# USB.net
KiCad netlist of a schematic drawn in Altium Designer
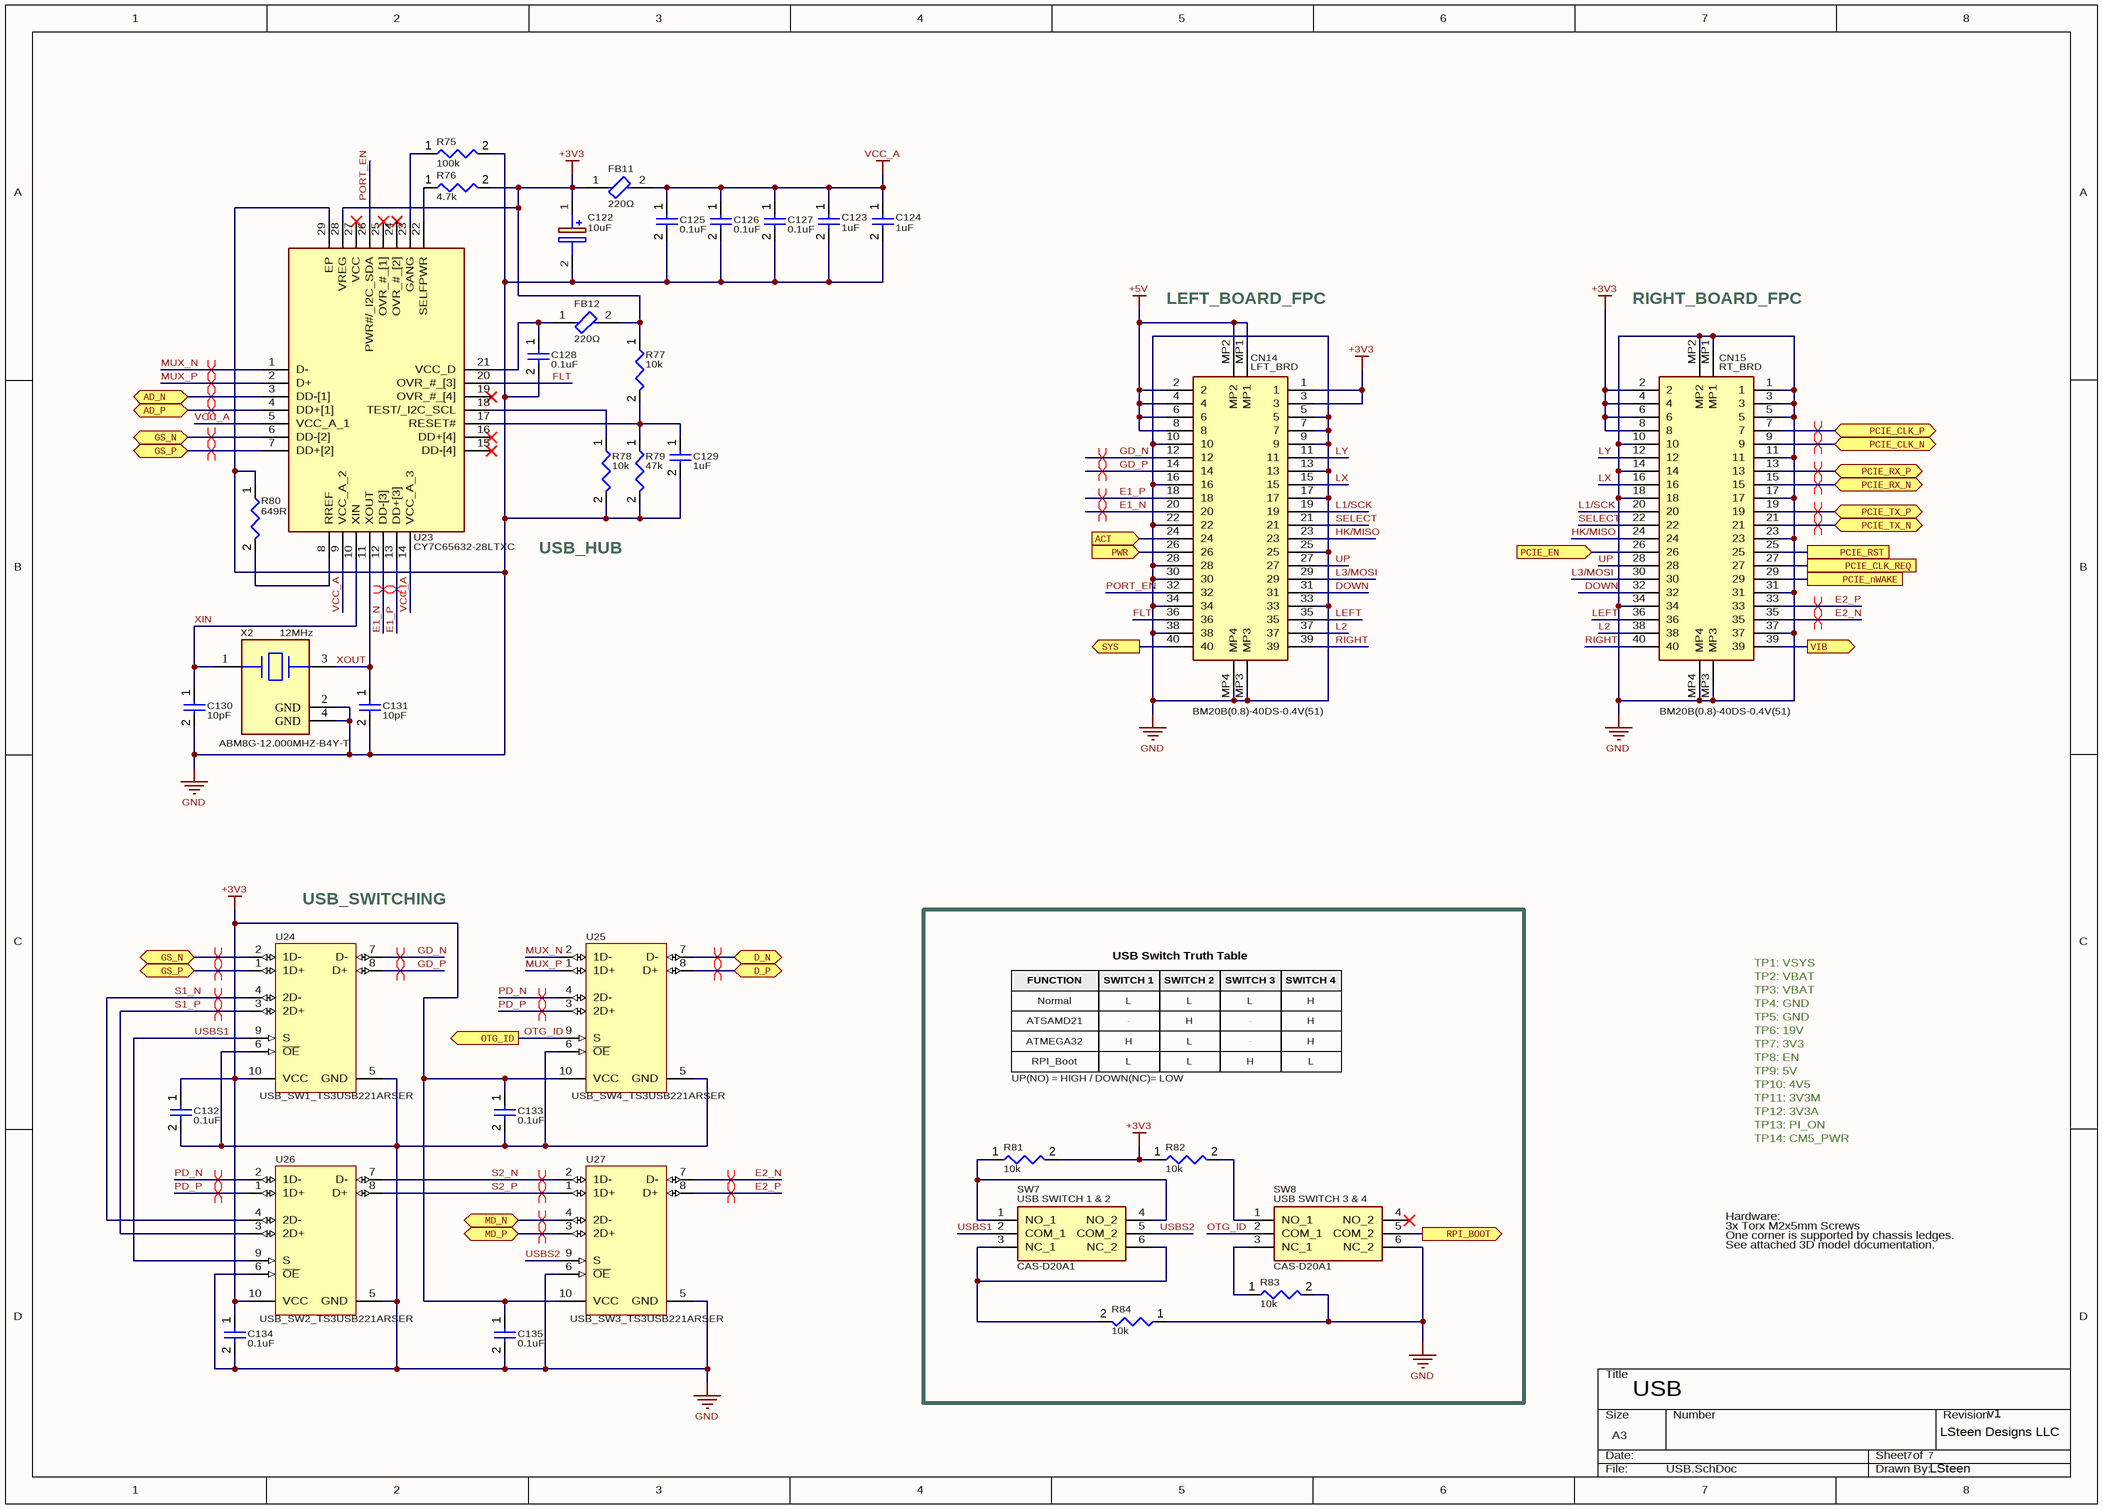
[diagram p0: USB.SchDoc]

(export (version "E")
  (design (tool "Eeschema 10.0.6"))
  (components
    (comp (ref "C122")
      (value "10uF")
      (footprint "SamacSys:CAPAE430X395N")
      (description "Capacitor Polarised")
      (fields
        (field (name "MANUFACTURER_PART_NUMBER") "UZG1C100MCL1GB")
        (field (name "MOUSER PART NUMBER") "647-UZG1C100MCL1GB")
      )
      (libsource (lib "SamacSys") (part "UZG1C100MCL1GB"))
    )
    (comp (ref "C123")
      (value "1uF")
      (footprint "CAPC0603(1608)100_L")
      (description "Chip Capacitor, 1uF +/-20%, 10V, 0603, Thickness 1 mm")
      (fields (field (name "TOLERANCE") "10%"))
      (libsource (lib "Colorado Technical University") (part "CAP-NP-2"))
    )
    (comp (ref "C124")
      (value "1uF")
      (footprint "CAPC0603(1608)100_L")
      (description "Chip Capacitor, 1uF +/-20%, 10V, 0603, Thickness 1 mm")
      (fields (field (name "TOLERANCE") "10%"))
      (libsource (lib "Colorado Technical University") (part "CAP-NP-2"))
    )
    (comp (ref "C125")
      (value "0.1uF")
      (footprint "CAPC1005X56X25LL10T15")
      (description "Chip Capacitor, 0.1 uF, +/- 5%, 16 V, 0402 (1005 Metric)")
      (fields (field (name "TOLERANCE") "5%"))
      (libsource (lib "Colorado Technical University") (part "CAP-NP-2"))
    )
    (comp (ref "C126")
      (value "0.1uF")
      (footprint "CAPC1005X56X25LL10T15")
      (description "Chip Capacitor, 0.1 uF, +/- 5%, 16 V, 0402 (1005 Metric)")
      (fields (field (name "TOLERANCE") "5%"))
      (libsource (lib "Colorado Technical University") (part "CAP-NP-2"))
    )
    (comp (ref "C127")
      (value "0.1uF")
      (footprint "CAPC1005X56X25LL10T15")
      (description "Chip Capacitor, 0.1 uF, +/- 5%, 16 V, 0402 (1005 Metric)")
      (fields (field (name "TOLERANCE") "5%"))
      (libsource (lib "Colorado Technical University") (part "CAP-NP-2"))
    )
    (comp (ref "C128")
      (value "0.1uF")
      (footprint "CAPC1005X56X25LL10T15")
      (description "Chip Capacitor, 0.1 uF, +/- 5%, 16 V, 0402 (1005 Metric)")
      (fields (field (name "TOLERANCE") "5%"))
      (libsource (lib "Colorado Technical University") (part "CAP-NP-2"))
    )
    (comp (ref "C129")
      (value "1uF")
      (footprint "CAPC0603(1608)100_L")
      (description "Chip Capacitor, 1uF +/-20%, 10V, 0603, Thickness 1 mm")
      (fields (field (name "TOLERANCE") "10%"))
      (libsource (lib "Colorado Technical University") (part "CAP-NP-2"))
    )
    (comp (ref "C130")
      (value "10pF")
      (footprint "CAPC1005X56X25LL10T15")
      (description "Chip Capacitor, 10 pF, +/- 5%, 16 V, 0402 (1005 Metric)")
      (fields (field (name "TOLERANCE") "5%"))
      (libsource (lib "Colorado Technical University") (part "CAP-NP-2"))
    )
    (comp (ref "C131")
      (value "10pF")
      (footprint "CAPC1005X56X25LL10T15")
      (description "Chip Capacitor, 10 pF, +/- 5%, 16 V, 0402 (1005 Metric)")
      (fields (field (name "TOLERANCE") "5%"))
      (libsource (lib "Colorado Technical University") (part "CAP-NP-2"))
    )
    (comp (ref "C132")
      (value "0.1uF")
      (footprint "CAPC1005X56X25LL10T15")
      (description "Chip Capacitor, 0.1 uF, +/- 5%, 16 V, 0402 (1005 Metric)")
      (fields (field (name "TOLERANCE") "5%"))
      (libsource (lib "Colorado Technical University") (part "CAP-NP-2"))
    )
    (comp (ref "C133")
      (value "0.1uF")
      (footprint "CAPC1005X56X25LL10T15")
      (description "Chip Capacitor, 0.1 uF, +/- 5%, 16 V, 0402 (1005 Metric)")
      (fields (field (name "TOLERANCE") "5%"))
      (libsource (lib "Colorado Technical University") (part "CAP-NP-2"))
    )
    (comp (ref "C134")
      (value "0.1uF")
      (footprint "CAPC1005X56X25LL10T15")
      (description "Chip Capacitor, 0.1 uF, +/- 5%, 16 V, 0402 (1005 Metric)")
      (fields (field (name "TOLERANCE") "5%"))
      (libsource (lib "Colorado Technical University") (part "CAP-NP-2"))
    )
    (comp (ref "C135")
      (value "0.1uF")
      (footprint "CAPC1005X56X25LL10T15")
      (description "Chip Capacitor, 0.1 uF, +/- 5%, 16 V, 0402 (1005 Metric)")
      (fields (field (name "TOLERANCE") "5%"))
      (libsource (lib "Colorado Technical University") (part "CAP-NP-2"))
    )
    (comp (ref "CN14")
      (value "LFT_BRD")
      (footprint "SamacSys:BM20B0840DS04V51")
      (description "Connector")
      (fields
        (field (name "MANUFACTURER_PART_NUMBER") "BM20B(0.8)-40DS-0.4V(51)")
        (field (name "MOUSER PART NUMBER") "798-BM20B0840DS04V51")
      )
      (libsource (lib "SamacSys") (part "BM20B(0.8)-40DS-0.4V(51)"))
    )
    (comp (ref "CN15")
      (value "RT_BRD")
      (footprint "SamacSys:BM20B0840DS04V51")
      (description "Connector")
      (fields
        (field (name "MANUFACTURER_PART_NUMBER") "BM20B(0.8)-40DS-0.4V(51)")
        (field (name "MOUSER PART NUMBER") "798-BM20B0840DS04V51")
      )
      (libsource (lib "SamacSys") (part "BM20B(0.8)-40DS-0.4V(51)"))
    )
    (comp (ref "FB11")
      (value "220Ω")
      (footprint "FP-BLM18-0_15-t0_5-IPC_B")
      (description "Chip Ferrite Bead, 0603, 220Ω @ 100MHz, 25%, 0.04Ω, 2.5A")
      (libsource (lib "Altium Content Vault") (part "5f30dd21d616792df468990f7003faa"))
    )
    (comp (ref "FB12")
      (value "220Ω")
      (footprint "FP-BLM18-0_15-t0_5-IPC_B")
      (description "Chip Ferrite Bead, 0603, 220Ω @ 100MHz, 25%, 0.04Ω, 2.5A")
      (libsource (lib "Altium Content Vault") (part "5f30dd21d616792df468990f7003faa"))
    )
    (comp (ref "R75")
      (value "100k")
      (footprint "RESC0402(1005)_L")
      (description "Chip Resistor, 100 kOhms, +/-5 %, 63 mW, -55 to 155 degC, 0402")
      (fields (field (name "TOLERANCE") "5%") (field (name "POWER") "63mW"))
      (libsource (lib "Colorado Technical University") (part "RES-2"))
    )
    (comp (ref "R76")
      (value "4.7k")
      (footprint "RESC0402(1005)_L")
      (description "Chip Resistor, 4.7 kOhms, +/-5 %, 63 mW, -55 to 155 degC, 0402")
      (fields (field (name "TOLERANCE") "5%") (field (name "POWER") "63mW"))
      (libsource (lib "Colorado Technical University") (part "RES-2"))
    )
    (comp (ref "R77")
      (value "10k")
      (footprint "RESC0402(1005)_L")
      (description "Chip Resistor, 10 kOhms, +/-5 %, 63 mW, -55 to 155 degC, 0402")
      (fields (field (name "TOLERANCE") "5%") (field (name "POWER") "63mW"))
      (libsource (lib "Colorado Technical University") (part "RES-2"))
    )
    (comp (ref "R78")
      (value "10k")
      (footprint "RESC0402(1005)_L")
      (description "Chip Resistor, 10 kOhms, +/-5 %, 63 mW, -55 to 155 degC, 0402")
      (fields (field (name "TOLERANCE") "5%") (field (name "POWER") "63mW"))
      (libsource (lib "Colorado Technical University") (part "RES-2"))
    )
    (comp (ref "R79")
      (value "47k")
      (footprint "RESC0402(1005)_L")
      (description "Chip Resistor, 47 kOhms, +/-5 %, 63 mW, -55 to 155 degC, 0402")
      (fields (field (name "TOLERANCE") "5%") (field (name "POWER") "63mW"))
      (libsource (lib "Colorado Technical University") (part "RES-2"))
    )
    (comp (ref "R80")
      (value "649R")
      (footprint "RESC0402(1005)_L")
      (description "Chip Resistor, 649 Ohms, +/-5 %, 63 mW, -55 to 155 degC, 0402")
      (fields (field (name "TOLERANCE") "5%") (field (name "POWER") "63mW"))
      (libsource (lib "Colorado Technical University") (part "RES-2"))
    )
    (comp (ref "R81")
      (value "10k")
      (footprint "RESC0402(1005)_L")
      (description "Chip Resistor, 10 kOhms, +/-5 %, 63 mW, -55 to 155 degC, 0402")
      (fields (field (name "TOLERANCE") "5%") (field (name "POWER") "63mW"))
      (libsource (lib "Colorado Technical University") (part "RES-2"))
    )
    (comp (ref "R82")
      (value "10k")
      (footprint "RESC0402(1005)_L")
      (description "Chip Resistor, 10 kOhms, +/-5 %, 63 mW, -55 to 155 degC, 0402")
      (fields (field (name "TOLERANCE") "5%") (field (name "POWER") "63mW"))
      (libsource (lib "Colorado Technical University") (part "RES-2"))
    )
    (comp (ref "R83")
      (value "10k")
      (footprint "RESC0402(1005)_L")
      (description "Chip Resistor, 10 kOhms, +/-5 %, 63 mW, -55 to 155 degC, 0402")
      (fields (field (name "TOLERANCE") "5%") (field (name "POWER") "63mW"))
      (libsource (lib "Colorado Technical University") (part "RES-2"))
    )
    (comp (ref "R84")
      (value "10k")
      (footprint "RESC0402(1005)_L")
      (description "Chip Resistor, 10 kOhms, +/-5 %, 63 mW, -55 to 155 degC, 0402")
      (fields (field (name "TOLERANCE") "5%") (field (name "POWER") "63mW"))
      (libsource (lib "Colorado Technical University") (part "RES-2"))
    )
    (comp (ref "SW7")
      (value "USB_SW1/SW2")
      (footprint "SamacSys:CASD20A1")
      (description "Switch")
      (fields (field (name "MANUFACTURER_PART_NUMBER") "CAS-D20A1"))
      (libsource (lib "SamacSys") (part "CAS-D20A1"))
    )
    (comp (ref "SW8")
      (value "USB_SW3/SW4")
      (footprint "SamacSys:CASD20A1")
      (description "Switch")
      (fields (field (name "MANUFACTURER_PART_NUMBER") "CAS-D20A1"))
      (libsource (lib "SamacSys") (part "CAS-D20A1"))
    )
    (comp (ref "U23")
      (value "CY7C65632-28LTXC")
      (footprint "SamacSys:QFN50P500X500X80-29N-D")
      (description "Integrated Circuit")
      (fields (field (name "MOUSER PART NUMBER") "727-CY7C65632-28LTXC"))
      (libsource (lib "SamacSys") (part "CY7C65632-28LTXC"))
    )
    (comp (ref "U24")
      (value "USB_SW1_TS3USB221ARSER")
      (footprint "RSE0010A_V")
      (fields (field (name "MANUFACTURER") "Texas Instruments") (field (name "PARTNUMBER") "TS3USB221ARSER"))
      (libsource (lib "Altium Content Vault") (part "TI-TS3USB221A-UQFN_RSE-10"))
    )
    (comp (ref "U25")
      (value "USB_SW4_TS3USB221ARSER")
      (footprint "RSE0010A_V")
      (fields (field (name "MANUFACTURER") "Texas Instruments") (field (name "PARTNUMBER") "TS3USB221ARSER"))
      (libsource (lib "Altium Content Vault") (part "TI-TS3USB221A-UQFN_RSE-10"))
    )
    (comp (ref "U26")
      (value "USB_SW2_TS3USB221ARSER")
      (footprint "RSE0010A_V")
      (fields (field (name "MANUFACTURER") "Texas Instruments") (field (name "PARTNUMBER") "TS3USB221ARSER"))
      (libsource (lib "Altium Content Vault") (part "TI-TS3USB221A-UQFN_RSE-10"))
    )
    (comp (ref "U27")
      (value "USB_SW3_TS3USB221ARSER")
      (footprint "RSE0010A_V")
      (fields (field (name "MANUFACTURER") "Texas Instruments") (field (name "PARTNUMBER") "TS3USB221ARSER"))
      (libsource (lib "Altium Content Vault") (part "TI-TS3USB221A-UQFN_RSE-10"))
    )
    (comp (ref "X2")
      (value "12MHz")
      (footprint "FP-ABM8G-MFG")
      (description "Crystal 12MHz ±30ppm (Tol) ±30ppm (Stability) 10pF FUND 120Ω 4-Pin SMD T/R")
      (fields (field (name "TOLERANCE") "30ppm"))
      (libsource (lib "Altium Content Vault") (part "48e526d86b7f2615d98721063c72f49"))
    )
  )
  (nets
    (net (code "1") (name "+3V3") (class "Default")
      (node (ref "C122") (pin "1") (pinfunction "+_1") (pintype "passive"))
      (node (ref "C132") (pin "1") (pinfunction "1_1") (pintype "passive"))
      (node (ref "C133") (pin "1") (pinfunction "1_1") (pintype "passive"))
      (node (ref "C134") (pin "1") (pinfunction "1_1") (pintype "passive"))
      (node (ref "C135") (pin "1") (pinfunction "1_1") (pintype "passive"))
      (node (ref "CN14") (pin "1") (pinfunction "1_1") (pintype "passive"))
      (node (ref "CN14") (pin "3") (pinfunction "3_3") (pintype "passive"))
      (node (ref "CN15") (pin "2") (pinfunction "2_2") (pintype "passive"))
      (node (ref "CN15") (pin "4") (pinfunction "4_4") (pintype "passive"))
      (node (ref "CN15") (pin "6") (pinfunction "6_6") (pintype "passive"))
      (node (ref "CN15") (pin "8") (pinfunction "8_8") (pintype "passive"))
      (node (ref "FB11") (pin "1") (pinfunction "1_1") (pintype "passive"))
      (node (ref "FB12") (pin "2") (pinfunction "2_2") (pintype "passive"))
      (node (ref "R76") (pin "2") (pinfunction "2_2") (pintype "passive"))
      (node (ref "R77") (pin "1") (pinfunction "1_1") (pintype "passive"))
      (node (ref "R81") (pin "2") (pinfunction "2_2") (pintype "passive"))
      (node (ref "R82") (pin "1") (pinfunction "1_1") (pintype "passive"))
      (node (ref "U23") (pin "28") (pinfunction "VREG_28") (pintype "passive"))
      (node (ref "U24") (pin "10") (pinfunction "VCC_10") (pintype "power_in"))
      (node (ref "U25") (pin "10") (pinfunction "VCC_10") (pintype "power_in"))
      (node (ref "U26") (pin "10") (pinfunction "VCC_10") (pintype "power_in"))
      (node (ref "U27") (pin "10") (pinfunction "VCC_10") (pintype "power_in"))
    )
    (net (code "2") (name "+5V") (class "Default")
      (node (ref "CN14") (pin "2") (pinfunction "2_2") (pintype "passive"))
      (node (ref "CN14") (pin "4") (pinfunction "4_4") (pintype "passive"))
      (node (ref "CN14") (pin "6") (pinfunction "6_6") (pintype "passive"))
      (node (ref "CN14") (pin "8") (pinfunction "8_8") (pintype "passive"))
      (node (ref "CN14") (pin "MP1") (pinfunction "MP1_MP1") (pintype "passive"))
      (node (ref "CN14") (pin "MP2") (pinfunction "MP2_MP2") (pintype "passive"))
    )
    (net (code "3") (name "/ACT") (class "Default")
      (node (ref "CN14") (pin "24") (pinfunction "24_24") (pintype "passive"))
    )
    (net (code "4") (name "/AD_N") (class "Default")
      (node (ref "U23") (pin "3") (pinfunction "DD-[1]_3") (pintype "passive"))
    )
    (net (code "5") (name "/AD_P") (class "Default")
      (node (ref "U23") (pin "4") (pinfunction "DD+[1]_4") (pintype "passive"))
    )
    (net (code "6") (name "/DOWN") (class "Default")
      (node (ref "CN14") (pin "31") (pinfunction "31_31") (pintype "passive"))
      (node (ref "CN15") (pin "32") (pinfunction "32_32") (pintype "passive"))
    )
    (net (code "7") (name "/D_N") (class "Default")
      (node (ref "U25") (pin "7") (pinfunction "D-_7") (pintype "bidirectional"))
    )
    (net (code "8") (name "/D_P") (class "Default")
      (node (ref "U25") (pin "8") (pinfunction "D+_8") (pintype "bidirectional"))
    )
    (net (code "9") (name "/E1_N") (class "Default")
      (node (ref "CN14") (pin "20") (pinfunction "20_20") (pintype "passive"))
      (node (ref "U23") (pin "12") (pinfunction "DD-[3]_12") (pintype "passive"))
    )
    (net (code "10") (name "/E1_P") (class "Default")
      (node (ref "CN14") (pin "18") (pinfunction "18_18") (pintype "passive"))
      (node (ref "U23") (pin "13") (pinfunction "DD+[3]_13") (pintype "passive"))
    )
    (net (code "11") (name "/E2_N") (class "Default")
      (node (ref "CN15") (pin "35") (pinfunction "35_35") (pintype "passive"))
      (node (ref "U27") (pin "7") (pinfunction "D-_7") (pintype "bidirectional"))
    )
    (net (code "12") (name "/E2_P") (class "Default")
      (node (ref "CN15") (pin "33") (pinfunction "33_33") (pintype "passive"))
      (node (ref "U27") (pin "8") (pinfunction "D+_8") (pintype "bidirectional"))
    )
    (net (code "13") (name "/FLT") (class "Default")
      (node (ref "CN14") (pin "36") (pinfunction "36_36") (pintype "passive"))
      (node (ref "U23") (pin "20") (pinfunction "OVR_#_[3]_20") (pintype "passive"))
    )
    (net (code "14") (name "/GD_N") (class "Default")
      (node (ref "CN14") (pin "12") (pinfunction "12_12") (pintype "passive"))
      (node (ref "U24") (pin "7") (pinfunction "D-_7") (pintype "bidirectional"))
    )
    (net (code "15") (name "/GD_P") (class "Default")
      (node (ref "CN14") (pin "14") (pinfunction "14_14") (pintype "passive"))
      (node (ref "U24") (pin "8") (pinfunction "D+_8") (pintype "bidirectional"))
    )
    (net (code "16") (name "/GS_N") (class "Default")
      (node (ref "U23") (pin "6") (pinfunction "DD-[2]_6") (pintype "passive"))
      (node (ref "U24") (pin "2") (pinfunction "1D-_2") (pintype "bidirectional"))
    )
    (net (code "17") (name "/GS_P") (class "Default")
      (node (ref "U23") (pin "7") (pinfunction "DD+[2]_7") (pintype "passive"))
      (node (ref "U24") (pin "1") (pinfunction "1D+_1") (pintype "bidirectional"))
    )
    (net (code "18") (name "/HK{slash}MISO") (class "Default")
      (node (ref "CN14") (pin "23") (pinfunction "23_23") (pintype "passive"))
      (node (ref "CN15") (pin "24") (pinfunction "24_24") (pintype "passive"))
    )
    (net (code "19") (name "/L1{slash}SCK") (class "Default")
      (node (ref "CN14") (pin "19") (pinfunction "19_19") (pintype "passive"))
      (node (ref "CN15") (pin "20") (pinfunction "20_20") (pintype "passive"))
    )
    (net (code "20") (name "/L2") (class "Default")
      (node (ref "CN14") (pin "37") (pinfunction "37_37") (pintype "passive"))
      (node (ref "CN15") (pin "38") (pinfunction "38_38") (pintype "passive"))
    )
    (net (code "21") (name "/L3{slash}MOSI") (class "Default")
      (node (ref "CN14") (pin "29") (pinfunction "29_29") (pintype "passive"))
      (node (ref "CN15") (pin "30") (pinfunction "30_30") (pintype "passive"))
    )
    (net (code "22") (name "/LEFT") (class "Default")
      (node (ref "CN14") (pin "35") (pinfunction "35_35") (pintype "passive"))
      (node (ref "CN15") (pin "36") (pinfunction "36_36") (pintype "passive"))
    )
    (net (code "23") (name "/LX") (class "Default")
      (node (ref "CN14") (pin "15") (pinfunction "15_15") (pintype "passive"))
      (node (ref "CN15") (pin "16") (pinfunction "16_16") (pintype "passive"))
    )
    (net (code "24") (name "/LY") (class "Default")
      (node (ref "CN14") (pin "11") (pinfunction "11_11") (pintype "passive"))
      (node (ref "CN15") (pin "12") (pinfunction "12_12") (pintype "passive"))
    )
    (net (code "25") (name "/MD_N") (class "Default")
      (node (ref "U27") (pin "4") (pinfunction "2D-_4") (pintype "bidirectional"))
    )
    (net (code "26") (name "/MD_P") (class "Default")
      (node (ref "U27") (pin "3") (pinfunction "2D+_3") (pintype "bidirectional"))
    )
    (net (code "27") (name "/MUX_N") (class "Default")
      (node (ref "U23") (pin "1") (pinfunction "D-_1") (pintype "passive"))
      (node (ref "U25") (pin "2") (pinfunction "1D-_2") (pintype "bidirectional"))
    )
    (net (code "28") (name "/MUX_P") (class "Default")
      (node (ref "U23") (pin "2") (pinfunction "D+_2") (pintype "passive"))
      (node (ref "U25") (pin "1") (pinfunction "1D+_1") (pintype "bidirectional"))
    )
    (net (code "29") (name "/OTG_ID") (class "Default")
      (node (ref "SW8") (pin "2") (pinfunction "COM_1_2") (pintype "passive"))
      (node (ref "U25") (pin "9") (pinfunction "S_9") (pintype "input"))
    )
    (net (code "30") (name "/PCIE_CLK_N") (class "Default")
      (node (ref "CN15") (pin "9") (pinfunction "9_9") (pintype "passive"))
    )
    (net (code "31") (name "/PCIE_CLK_P") (class "Default")
      (node (ref "CN15") (pin "7") (pinfunction "7_7") (pintype "passive"))
    )
    (net (code "32") (name "/PCIE_CLK_REQ") (class "Default")
      (node (ref "CN15") (pin "27") (pinfunction "27_27") (pintype "passive"))
    )
    (net (code "33") (name "/PCIE_EN") (class "Default")
      (node (ref "CN15") (pin "26") (pinfunction "26_26") (pintype "passive"))
    )
    (net (code "34") (name "/PCIE_RST") (class "Default")
      (node (ref "CN15") (pin "25") (pinfunction "25_25") (pintype "passive"))
    )
    (net (code "35") (name "/PCIE_RX_N") (class "Default")
      (node (ref "CN15") (pin "15") (pinfunction "15_15") (pintype "passive"))
    )
    (net (code "36") (name "/PCIE_RX_P") (class "Default")
      (node (ref "CN15") (pin "13") (pinfunction "13_13") (pintype "passive"))
    )
    (net (code "37") (name "/PCIE_TX_N") (class "Default")
      (node (ref "CN15") (pin "21") (pinfunction "21_21") (pintype "passive"))
    )
    (net (code "38") (name "/PCIE_TX_P") (class "Default")
      (node (ref "CN15") (pin "19") (pinfunction "19_19") (pintype "passive"))
    )
    (net (code "39") (name "/PCIE_nWAKE") (class "Default")
      (node (ref "CN15") (pin "29") (pinfunction "29_29") (pintype "passive"))
    )
    (net (code "40") (name "/PD_N") (class "Default")
      (node (ref "U25") (pin "4") (pinfunction "2D-_4") (pintype "bidirectional"))
      (node (ref "U26") (pin "2") (pinfunction "1D-_2") (pintype "bidirectional"))
    )
    (net (code "41") (name "/PD_P") (class "Default")
      (node (ref "U25") (pin "3") (pinfunction "2D+_3") (pintype "bidirectional"))
      (node (ref "U26") (pin "1") (pinfunction "1D+_1") (pintype "bidirectional"))
    )
    (net (code "42") (name "/PORT_EN") (class "Default")
      (node (ref "CN14") (pin "32") (pinfunction "32_32") (pintype "passive"))
      (node (ref "U23") (pin "26") (pinfunction "PWR#/_I2C_SDA_26") (pintype "passive"))
    )
    (net (code "43") (name "/PWR") (class "Default")
      (node (ref "CN14") (pin "26") (pinfunction "26_26") (pintype "passive"))
    )
    (net (code "44") (name "/RIGHT") (class "Default")
      (node (ref "CN14") (pin "39") (pinfunction "39_39") (pintype "passive"))
      (node (ref "CN15") (pin "40") (pinfunction "40_40") (pintype "passive"))
    )
    (net (code "45") (name "/RPI_BOOT") (class "Default")
      (node (ref "SW8") (pin "5") (pinfunction "COM_2_5") (pintype "passive"))
    )
    (net (code "46") (name "/S1_N") (class "Default")
      (node (ref "U24") (pin "4") (pinfunction "2D-_4") (pintype "bidirectional"))
      (node (ref "U26") (pin "4") (pinfunction "2D-_4") (pintype "bidirectional"))
    )
    (net (code "47") (name "/S1_P") (class "Default")
      (node (ref "U24") (pin "3") (pinfunction "2D+_3") (pintype "bidirectional"))
      (node (ref "U26") (pin "3") (pinfunction "2D+_3") (pintype "bidirectional"))
    )
    (net (code "48") (name "/S2_N") (class "Default")
      (node (ref "U26") (pin "7") (pinfunction "D-_7") (pintype "bidirectional"))
      (node (ref "U27") (pin "2") (pinfunction "1D-_2") (pintype "bidirectional"))
    )
    (net (code "49") (name "/S2_P") (class "Default")
      (node (ref "U26") (pin "8") (pinfunction "D+_8") (pintype "bidirectional"))
      (node (ref "U27") (pin "1") (pinfunction "1D+_1") (pintype "bidirectional"))
    )
    (net (code "50") (name "/SELECT") (class "Default")
      (node (ref "CN14") (pin "21") (pinfunction "21_21") (pintype "passive"))
      (node (ref "CN15") (pin "22") (pinfunction "22_22") (pintype "passive"))
    )
    (net (code "51") (name "/SYS") (class "Default")
      (node (ref "CN14") (pin "40") (pinfunction "40_40") (pintype "passive"))
    )
    (net (code "52") (name "/UP") (class "Default")
      (node (ref "CN14") (pin "27") (pinfunction "27_27") (pintype "passive"))
      (node (ref "CN15") (pin "28") (pinfunction "28_28") (pintype "passive"))
    )
    (net (code "53") (name "/USBS1") (class "Default")
      (node (ref "SW7") (pin "2") (pinfunction "COM_1_2") (pintype "passive"))
      (node (ref "U24") (pin "9") (pinfunction "S_9") (pintype "input"))
      (node (ref "U26") (pin "9") (pinfunction "S_9") (pintype "input"))
    )
    (net (code "54") (name "/USBS2") (class "Default")
      (node (ref "SW7") (pin "5") (pinfunction "COM_2_5") (pintype "passive"))
      (node (ref "U27") (pin "9") (pinfunction "S_9") (pintype "input"))
    )
    (net (code "55") (name "/VIB") (class "Default")
      (node (ref "CN15") (pin "39") (pinfunction "39_39") (pintype "passive"))
    )
    (net (code "56") (name "/XIN") (class "Default")
      (node (ref "C130") (pin "1") (pinfunction "1_1") (pintype "passive"))
      (node (ref "U23") (pin "10") (pinfunction "XIN_10") (pintype "passive"))
      (node (ref "X2") (pin "1") (pinfunction "1_1") (pintype "passive"))
    )
    (net (code "57") (name "/XOUT") (class "Default")
      (node (ref "C131") (pin "1") (pinfunction "1_1") (pintype "passive"))
      (node (ref "U23") (pin "11") (pinfunction "XOUT_11") (pintype "passive"))
      (node (ref "X2") (pin "3") (pinfunction "3_3") (pintype "passive"))
    )
    (net (code "58") (name "GND") (class "Default")
      (node (ref "C122") (pin "2") (pinfunction "-_2") (pintype "passive"))
      (node (ref "C123") (pin "2") (pinfunction "2_2") (pintype "passive"))
      (node (ref "C124") (pin "2") (pinfunction "2_2") (pintype "passive"))
      (node (ref "C125") (pin "2") (pinfunction "2_2") (pintype "passive"))
      (node (ref "C126") (pin "2") (pinfunction "2_2") (pintype "passive"))
      (node (ref "C127") (pin "2") (pinfunction "2_2") (pintype "passive"))
      (node (ref "C128") (pin "2") (pinfunction "2_2") (pintype "passive"))
      (node (ref "C129") (pin "2") (pinfunction "2_2") (pintype "passive"))
      (node (ref "C130") (pin "2") (pinfunction "2_2") (pintype "passive"))
      (node (ref "C131") (pin "2") (pinfunction "2_2") (pintype "passive"))
      (node (ref "C132") (pin "2") (pinfunction "2_2") (pintype "passive"))
      (node (ref "C133") (pin "2") (pinfunction "2_2") (pintype "passive"))
      (node (ref "C134") (pin "2") (pinfunction "2_2") (pintype "passive"))
      (node (ref "C135") (pin "2") (pinfunction "2_2") (pintype "passive"))
      (node (ref "CN14") (pin "10") (pinfunction "10_10") (pintype "passive"))
      (node (ref "CN14") (pin "13") (pinfunction "13_13") (pintype "passive"))
      (node (ref "CN14") (pin "16") (pinfunction "16_16") (pintype "passive"))
      (node (ref "CN14") (pin "17") (pinfunction "17_17") (pintype "passive"))
      (node (ref "CN14") (pin "22") (pinfunction "22_22") (pintype "passive"))
      (node (ref "CN14") (pin "25") (pinfunction "25_25") (pintype "passive"))
      (node (ref "CN14") (pin "28") (pinfunction "28_28") (pintype "passive"))
      (node (ref "CN14") (pin "30") (pinfunction "30_30") (pintype "passive"))
      (node (ref "CN14") (pin "33") (pinfunction "33_33") (pintype "passive"))
      (node (ref "CN14") (pin "34") (pinfunction "34_34") (pintype "passive"))
      (node (ref "CN14") (pin "38") (pinfunction "38_38") (pintype "passive"))
      (node (ref "CN14") (pin "5") (pinfunction "5_5") (pintype "passive"))
      (node (ref "CN14") (pin "7") (pinfunction "7_7") (pintype "passive"))
      (node (ref "CN14") (pin "9") (pinfunction "9_9") (pintype "passive"))
      (node (ref "CN14") (pin "MP3") (pinfunction "MP3_MP3") (pintype "passive"))
      (node (ref "CN14") (pin "MP4") (pinfunction "MP4_MP4") (pintype "passive"))
      (node (ref "CN15") (pin "1") (pinfunction "1_1") (pintype "passive"))
      (node (ref "CN15") (pin "10") (pinfunction "10_10") (pintype "passive"))
      (node (ref "CN15") (pin "11") (pinfunction "11_11") (pintype "passive"))
      (node (ref "CN15") (pin "14") (pinfunction "14_14") (pintype "passive"))
      (node (ref "CN15") (pin "17") (pinfunction "17_17") (pintype "passive"))
      (node (ref "CN15") (pin "18") (pinfunction "18_18") (pintype "passive"))
      (node (ref "CN15") (pin "23") (pinfunction "23_23") (pintype "passive"))
      (node (ref "CN15") (pin "3") (pinfunction "3_3") (pintype "passive"))
      (node (ref "CN15") (pin "31") (pinfunction "31_31") (pintype "passive"))
      (node (ref "CN15") (pin "34") (pinfunction "34_34") (pintype "passive"))
      (node (ref "CN15") (pin "37") (pinfunction "37_37") (pintype "passive"))
      (node (ref "CN15") (pin "5") (pinfunction "5_5") (pintype "passive"))
      (node (ref "CN15") (pin "MP1") (pinfunction "MP1_MP1") (pintype "passive"))
      (node (ref "CN15") (pin "MP2") (pinfunction "MP2_MP2") (pintype "passive"))
      (node (ref "CN15") (pin "MP3") (pinfunction "MP3_MP3") (pintype "passive"))
      (node (ref "CN15") (pin "MP4") (pinfunction "MP4_MP4") (pintype "passive"))
      (node (ref "R75") (pin "2") (pinfunction "2_2") (pintype "passive"))
      (node (ref "R78") (pin "2") (pinfunction "2_2") (pintype "passive"))
      (node (ref "R79") (pin "2") (pinfunction "2_2") (pintype "passive"))
      (node (ref "R80") (pin "1") (pinfunction "1_1") (pintype "passive"))
      (node (ref "R83") (pin "2") (pinfunction "2_2") (pintype "passive"))
      (node (ref "R84") (pin "1") (pinfunction "1_1") (pintype "passive"))
      (node (ref "SW8") (pin "6") (pinfunction "NC_2_6") (pintype "passive"))
      (node (ref "U23") (pin "29") (pinfunction "EP_29") (pintype "passive"))
      (node (ref "U24") (pin "5") (pinfunction "GND_5") (pintype "power_in"))
      (node (ref "U24") (pin "6") (pinfunction "~{OE}_6") (pintype "input"))
      (node (ref "U25") (pin "5") (pinfunction "GND_5") (pintype "power_in"))
      (node (ref "U25") (pin "6") (pinfunction "~{OE}_6") (pintype "input"))
      (node (ref "U26") (pin "5") (pinfunction "GND_5") (pintype "power_in"))
      (node (ref "U26") (pin "6") (pinfunction "~{OE}_6") (pintype "input"))
      (node (ref "U27") (pin "5") (pinfunction "GND_5") (pintype "power_in"))
      (node (ref "U27") (pin "6") (pinfunction "~{OE}_6") (pintype "input"))
      (node (ref "X2") (pin "2") (pinfunction "GND_2") (pintype "power_in"))
      (node (ref "X2") (pin "4") (pinfunction "GND_4") (pintype "power_in"))
    )
    (net (code "59") (name "Net-(SW7-NC_1)") (class "Default")
      (node (ref "R84") (pin "2") (pinfunction "2_2") (pintype "passive"))
      (node (ref "SW7") (pin "3") (pinfunction "NC_1_3") (pintype "passive"))
      (node (ref "SW7") (pin "6") (pinfunction "NC_2_6") (pintype "passive"))
    )
    (net (code "60") (name "Net-(SW7-NO_1)") (class "Default")
      (node (ref "R81") (pin "1") (pinfunction "1_1") (pintype "passive"))
      (node (ref "SW7") (pin "1") (pinfunction "NO_1_1") (pintype "passive"))
      (node (ref "SW7") (pin "4") (pinfunction "NO_2_4") (pintype "passive"))
    )
    (net (code "61") (name "Net-(SW8-NC_1)") (class "Default")
      (node (ref "R83") (pin "1") (pinfunction "1_1") (pintype "passive"))
      (node (ref "SW8") (pin "3") (pinfunction "NC_1_3") (pintype "passive"))
    )
    (net (code "62") (name "Net-(SW8-NO_1)") (class "Default")
      (node (ref "R82") (pin "2") (pinfunction "2_2") (pintype "passive"))
      (node (ref "SW8") (pin "1") (pinfunction "NO_1_1") (pintype "passive"))
    )
    (net (code "63") (name "Net-(U23-GANG)") (class "Default")
      (node (ref "R75") (pin "1") (pinfunction "1_1") (pintype "passive"))
      (node (ref "U23") (pin "23") (pinfunction "GANG_23") (pintype "passive"))
    )
    (net (code "64") (name "Net-(U23-RESET#)") (class "Default")
      (node (ref "C129") (pin "1") (pinfunction "1_1") (pintype "passive"))
      (node (ref "R77") (pin "2") (pinfunction "2_2") (pintype "passive"))
      (node (ref "R79") (pin "1") (pinfunction "1_1") (pintype "passive"))
      (node (ref "U23") (pin "17") (pinfunction "RESET#_17") (pintype "passive"))
    )
    (net (code "65") (name "Net-(U23-RREF)") (class "Default")
      (node (ref "R80") (pin "2") (pinfunction "2_2") (pintype "passive"))
      (node (ref "U23") (pin "8") (pinfunction "RREF_8") (pintype "passive"))
    )
    (net (code "66") (name "Net-(U23-SELFPWR)") (class "Default")
      (node (ref "R76") (pin "1") (pinfunction "1_1") (pintype "passive"))
      (node (ref "U23") (pin "22") (pinfunction "SELFPWR_22") (pintype "passive"))
    )
    (net (code "67") (name "Net-(U23-TEST{slash}_I2C_SCL)") (class "Default")
      (node (ref "R78") (pin "1") (pinfunction "1_1") (pintype "passive"))
      (node (ref "U23") (pin "18") (pinfunction "TEST/_I2C_SCL_18") (pintype "passive"))
    )
    (net (code "68") (name "Net-(U23-VCC_D)") (class "Default")
      (node (ref "C128") (pin "1") (pinfunction "1_1") (pintype "passive"))
      (node (ref "FB12") (pin "1") (pinfunction "1_1") (pintype "passive"))
      (node (ref "U23") (pin "21") (pinfunction "VCC_D_21") (pintype "passive"))
    )
    (net (code "69") (name "VCC_A") (class "Default")
      (node (ref "C123") (pin "1") (pinfunction "1_1") (pintype "passive"))
      (node (ref "C124") (pin "1") (pinfunction "1_1") (pintype "passive"))
      (node (ref "C125") (pin "1") (pinfunction "1_1") (pintype "passive"))
      (node (ref "C126") (pin "1") (pinfunction "1_1") (pintype "passive"))
      (node (ref "C127") (pin "1") (pinfunction "1_1") (pintype "passive"))
      (node (ref "FB11") (pin "2") (pinfunction "2_2") (pintype "passive"))
      (node (ref "U23") (pin "14") (pinfunction "VCC_A_3_14") (pintype "passive"))
      (node (ref "U23") (pin "5") (pinfunction "VCC_A_1_5") (pintype "passive"))
      (node (ref "U23") (pin "9") (pinfunction "VCC_A_2_9") (pintype "passive"))
    )
    (net (code "70") (name "unconnected-(SW8-NO_2-Pad4)") (class "Default")
      (node (ref "SW8") (pin "4") (pinfunction "NO_2_4") (pintype "passive+no_connect"))
    )
    (net (code "71") (name "unconnected-(U23-DD+[4]-Pad16)") (class "Default")
      (node (ref "U23") (pin "16") (pinfunction "DD+[4]_16") (pintype "passive+no_connect"))
    )
    (net (code "72") (name "unconnected-(U23-DD-[4]-Pad15)") (class "Default")
      (node (ref "U23") (pin "15") (pinfunction "DD-[4]_15") (pintype "passive+no_connect"))
    )
    (net (code "73") (name "unconnected-(U23-OVR_#_[1]-Pad25)") (class "Default")
      (node (ref "U23") (pin "25") (pinfunction "OVR_#_[1]_25") (pintype "passive+no_connect"))
    )
    (net (code "74") (name "unconnected-(U23-OVR_#_[2]-Pad24)") (class "Default")
      (node (ref "U23") (pin "24") (pinfunction "OVR_#_[2]_24") (pintype "passive+no_connect"))
    )
    (net (code "75") (name "unconnected-(U23-OVR_#_[4]-Pad19)") (class "Default")
      (node (ref "U23") (pin "19") (pinfunction "OVR_#_[4]_19") (pintype "passive+no_connect"))
    )
    (net (code "76") (name "unconnected-(U23-VCC-Pad27)") (class "Default")
      (node (ref "U23") (pin "27") (pinfunction "VCC_27") (pintype "passive+no_connect"))
    )
  )
)
